# Qwiic_Module_for_Tessel_2.net
KiCad netlist of a schematic drawn in EAGLE
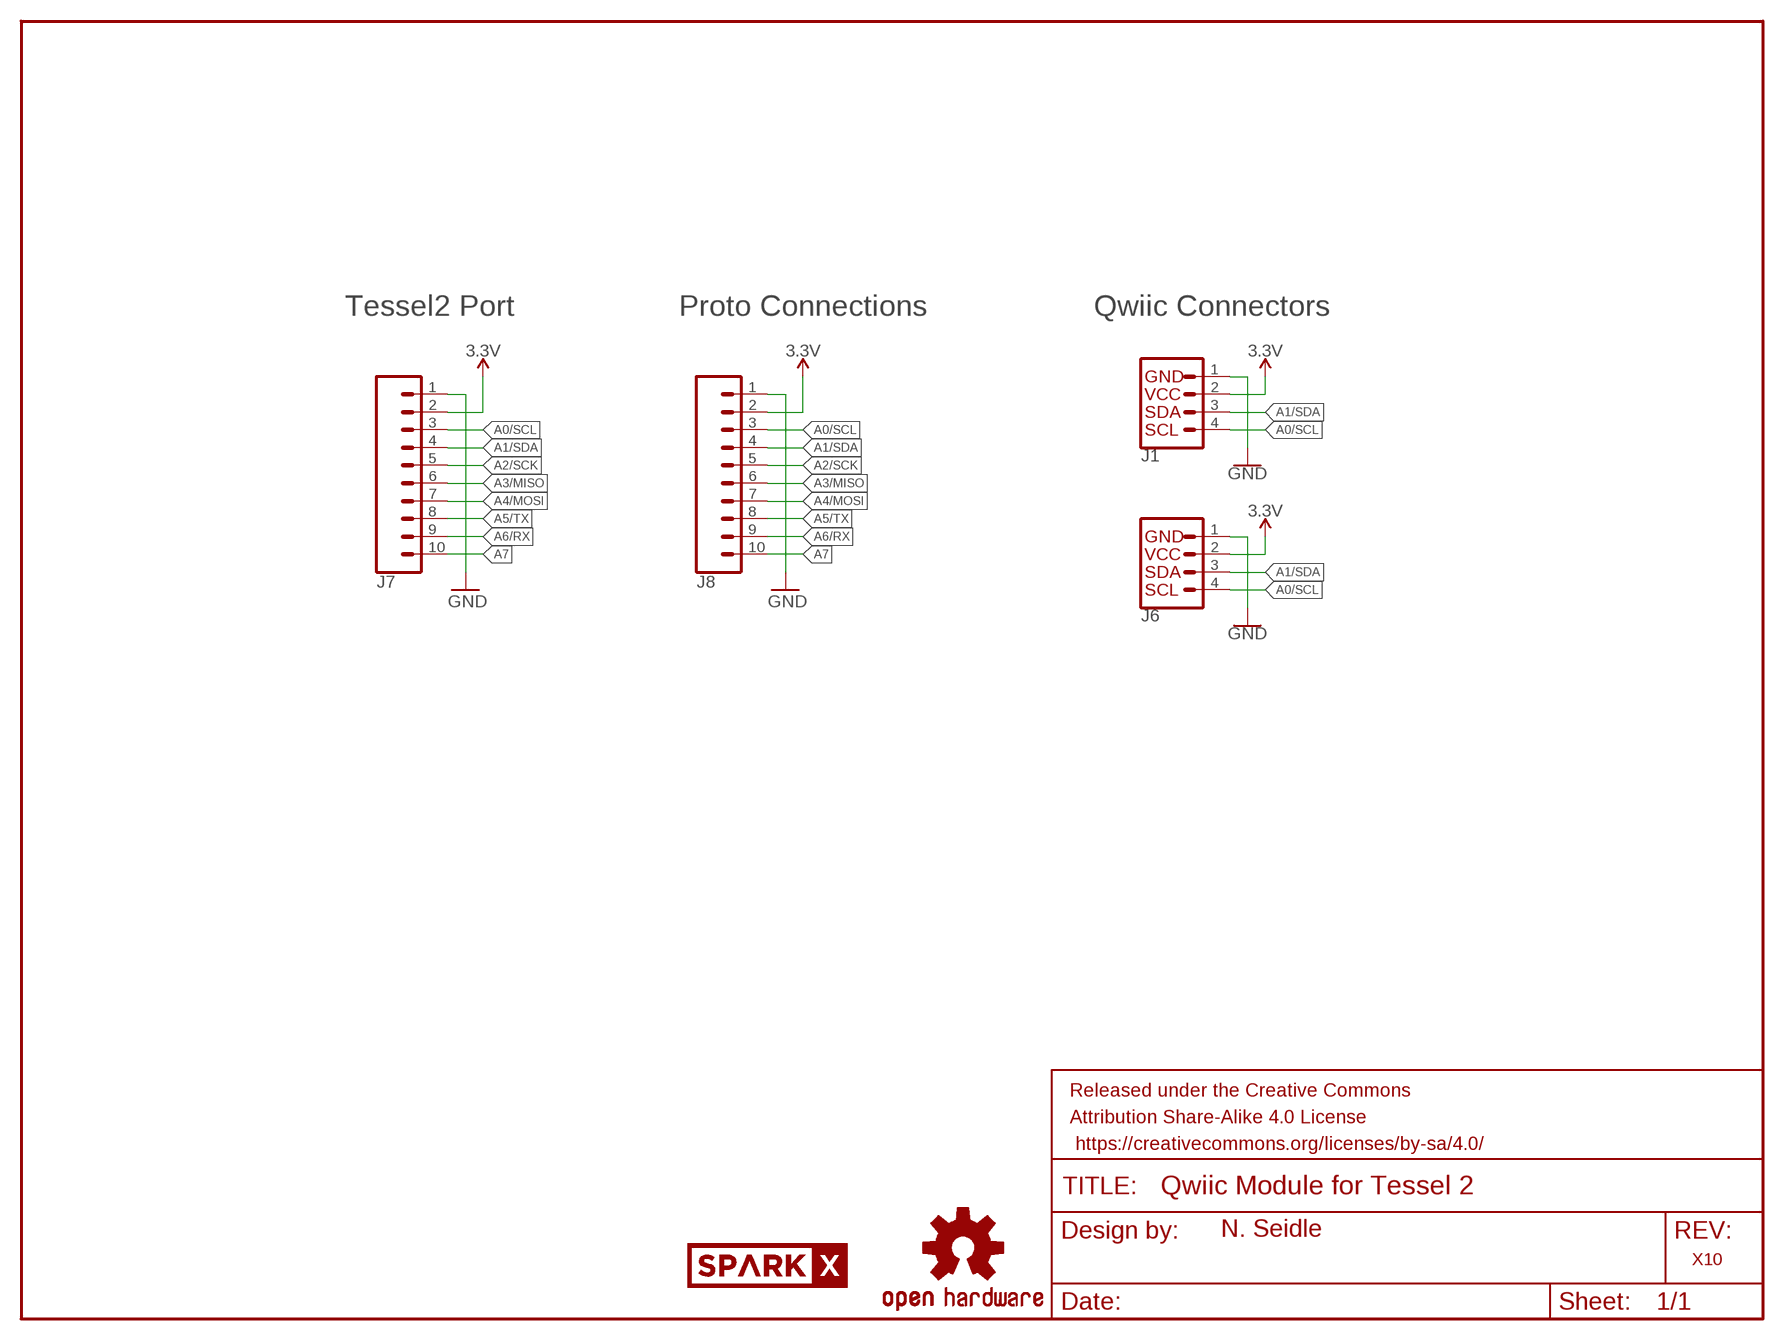
[diagram p0: schematic, sheet 1]

(export (version "E")
  (design (tool "Eeschema 10.0.6"))
  (components
    (comp (ref "FRAME1")
      (value "FRAME-LETTER")
      (footprint "eagle-import:CREATIVE_COMMONS")
      (libsource (lib "eagle-import") (part "FRAME-LETTER"))
    )
    (comp (ref "J1")
      (value "I2C_STANDARDJS-1MM")
      (footprint "eagle-import:1X04_1MM_RA")
      (libsource (lib "eagle-import") (part "I2C_STANDARDJS-1MM"))
    )
    (comp (ref "J6")
      (value "I2C_STANDARDJS-1MM")
      (footprint "eagle-import:1X04_1MM_RA")
      (libsource (lib "eagle-import") (part "I2C_STANDARDJS-1MM"))
    )
    (comp (ref "J7")
      (value "CONN_10NO_SILK_PTH_FEMALE")
      (footprint "eagle-import:1X10_NO_SILK")
      (libsource (lib "eagle-import") (part "CONN_10NO_SILK_PTH_FEMALE"))
    )
    (comp (ref "J8")
      (value "CONN_10NO_SILK_PTH_FEMALE")
      (footprint "eagle-import:1X10_NO_SILK")
      (libsource (lib "eagle-import") (part "CONN_10NO_SILK_PTH_FEMALE"))
    )
    (comp (ref "LOGO1")
      (value "OSHW-LOGOMINI")
      (footprint "eagle-import:OSHW-LOGO-MINI")
      (libsource (lib "eagle-import") (part "OSHW-LOGOMINI"))
    )
    (comp (ref "U$2")
      (value "SPARKX-LOGO4")
      (footprint "eagle-import:SPARKX-MEDIUM")
      (libsource (lib "eagle-import") (part "SPARKX-LOGO4"))
    )
  )
  (nets
    (net (code "1") (name "3.3V") (class "Default")
      (node (ref "J1") (pin "2") (pinfunction "VCC_2") (pintype "power_in"))
      (node (ref "J6") (pin "2") (pinfunction "VCC_2") (pintype "power_in"))
      (node (ref "J7") (pin "2") (pinfunction "2_2") (pintype "passive"))
      (node (ref "J8") (pin "2") (pinfunction "2_2") (pintype "passive"))
    )
    (net (code "2") (name "A0{slash}SCL") (class "Default")
      (node (ref "J1") (pin "4") (pinfunction "SCL_4") (pintype "passive"))
      (node (ref "J6") (pin "4") (pinfunction "SCL_4") (pintype "passive"))
      (node (ref "J7") (pin "3") (pinfunction "3_3") (pintype "passive"))
      (node (ref "J8") (pin "3") (pinfunction "3_3") (pintype "passive"))
    )
    (net (code "3") (name "A1{slash}SDA") (class "Default")
      (node (ref "J1") (pin "3") (pinfunction "SDA_3") (pintype "passive"))
      (node (ref "J6") (pin "3") (pinfunction "SDA_3") (pintype "passive"))
      (node (ref "J7") (pin "4") (pinfunction "4_4") (pintype "passive"))
      (node (ref "J8") (pin "4") (pinfunction "4_4") (pintype "passive"))
    )
    (net (code "4") (name "A2{slash}SCK") (class "Default")
      (node (ref "J7") (pin "5") (pinfunction "5_5") (pintype "passive"))
      (node (ref "J8") (pin "5") (pinfunction "5_5") (pintype "passive"))
    )
    (net (code "5") (name "A3{slash}MISO") (class "Default")
      (node (ref "J7") (pin "6") (pinfunction "6_6") (pintype "passive"))
      (node (ref "J8") (pin "6") (pinfunction "6_6") (pintype "passive"))
    )
    (net (code "6") (name "A4{slash}MOSI") (class "Default")
      (node (ref "J7") (pin "7") (pinfunction "7_7") (pintype "passive"))
      (node (ref "J8") (pin "7") (pinfunction "7_7") (pintype "passive"))
    )
    (net (code "7") (name "A5{slash}TX") (class "Default")
      (node (ref "J7") (pin "8") (pinfunction "8_8") (pintype "passive"))
      (node (ref "J8") (pin "8") (pinfunction "8_8") (pintype "passive"))
    )
    (net (code "8") (name "A6{slash}RX") (class "Default")
      (node (ref "J7") (pin "9") (pinfunction "9_9") (pintype "passive"))
      (node (ref "J8") (pin "9") (pinfunction "9_9") (pintype "passive"))
    )
    (net (code "9") (name "A7") (class "Default")
      (node (ref "J7") (pin "10") (pinfunction "10_10") (pintype "passive"))
      (node (ref "J8") (pin "10") (pinfunction "10_10") (pintype "passive"))
    )
    (net (code "10") (name "GND") (class "Default")
      (node (ref "J1") (pin "1") (pinfunction "GND_1") (pintype "power_in"))
      (node (ref "J6") (pin "1") (pinfunction "GND_1") (pintype "power_in"))
      (node (ref "J7") (pin "1") (pinfunction "1_1") (pintype "passive"))
      (node (ref "J8") (pin "1") (pinfunction "1_1") (pintype "passive"))
    )
  )
)
